# CAN.net
KiCad netlist of a schematic drawn in Altium Designer
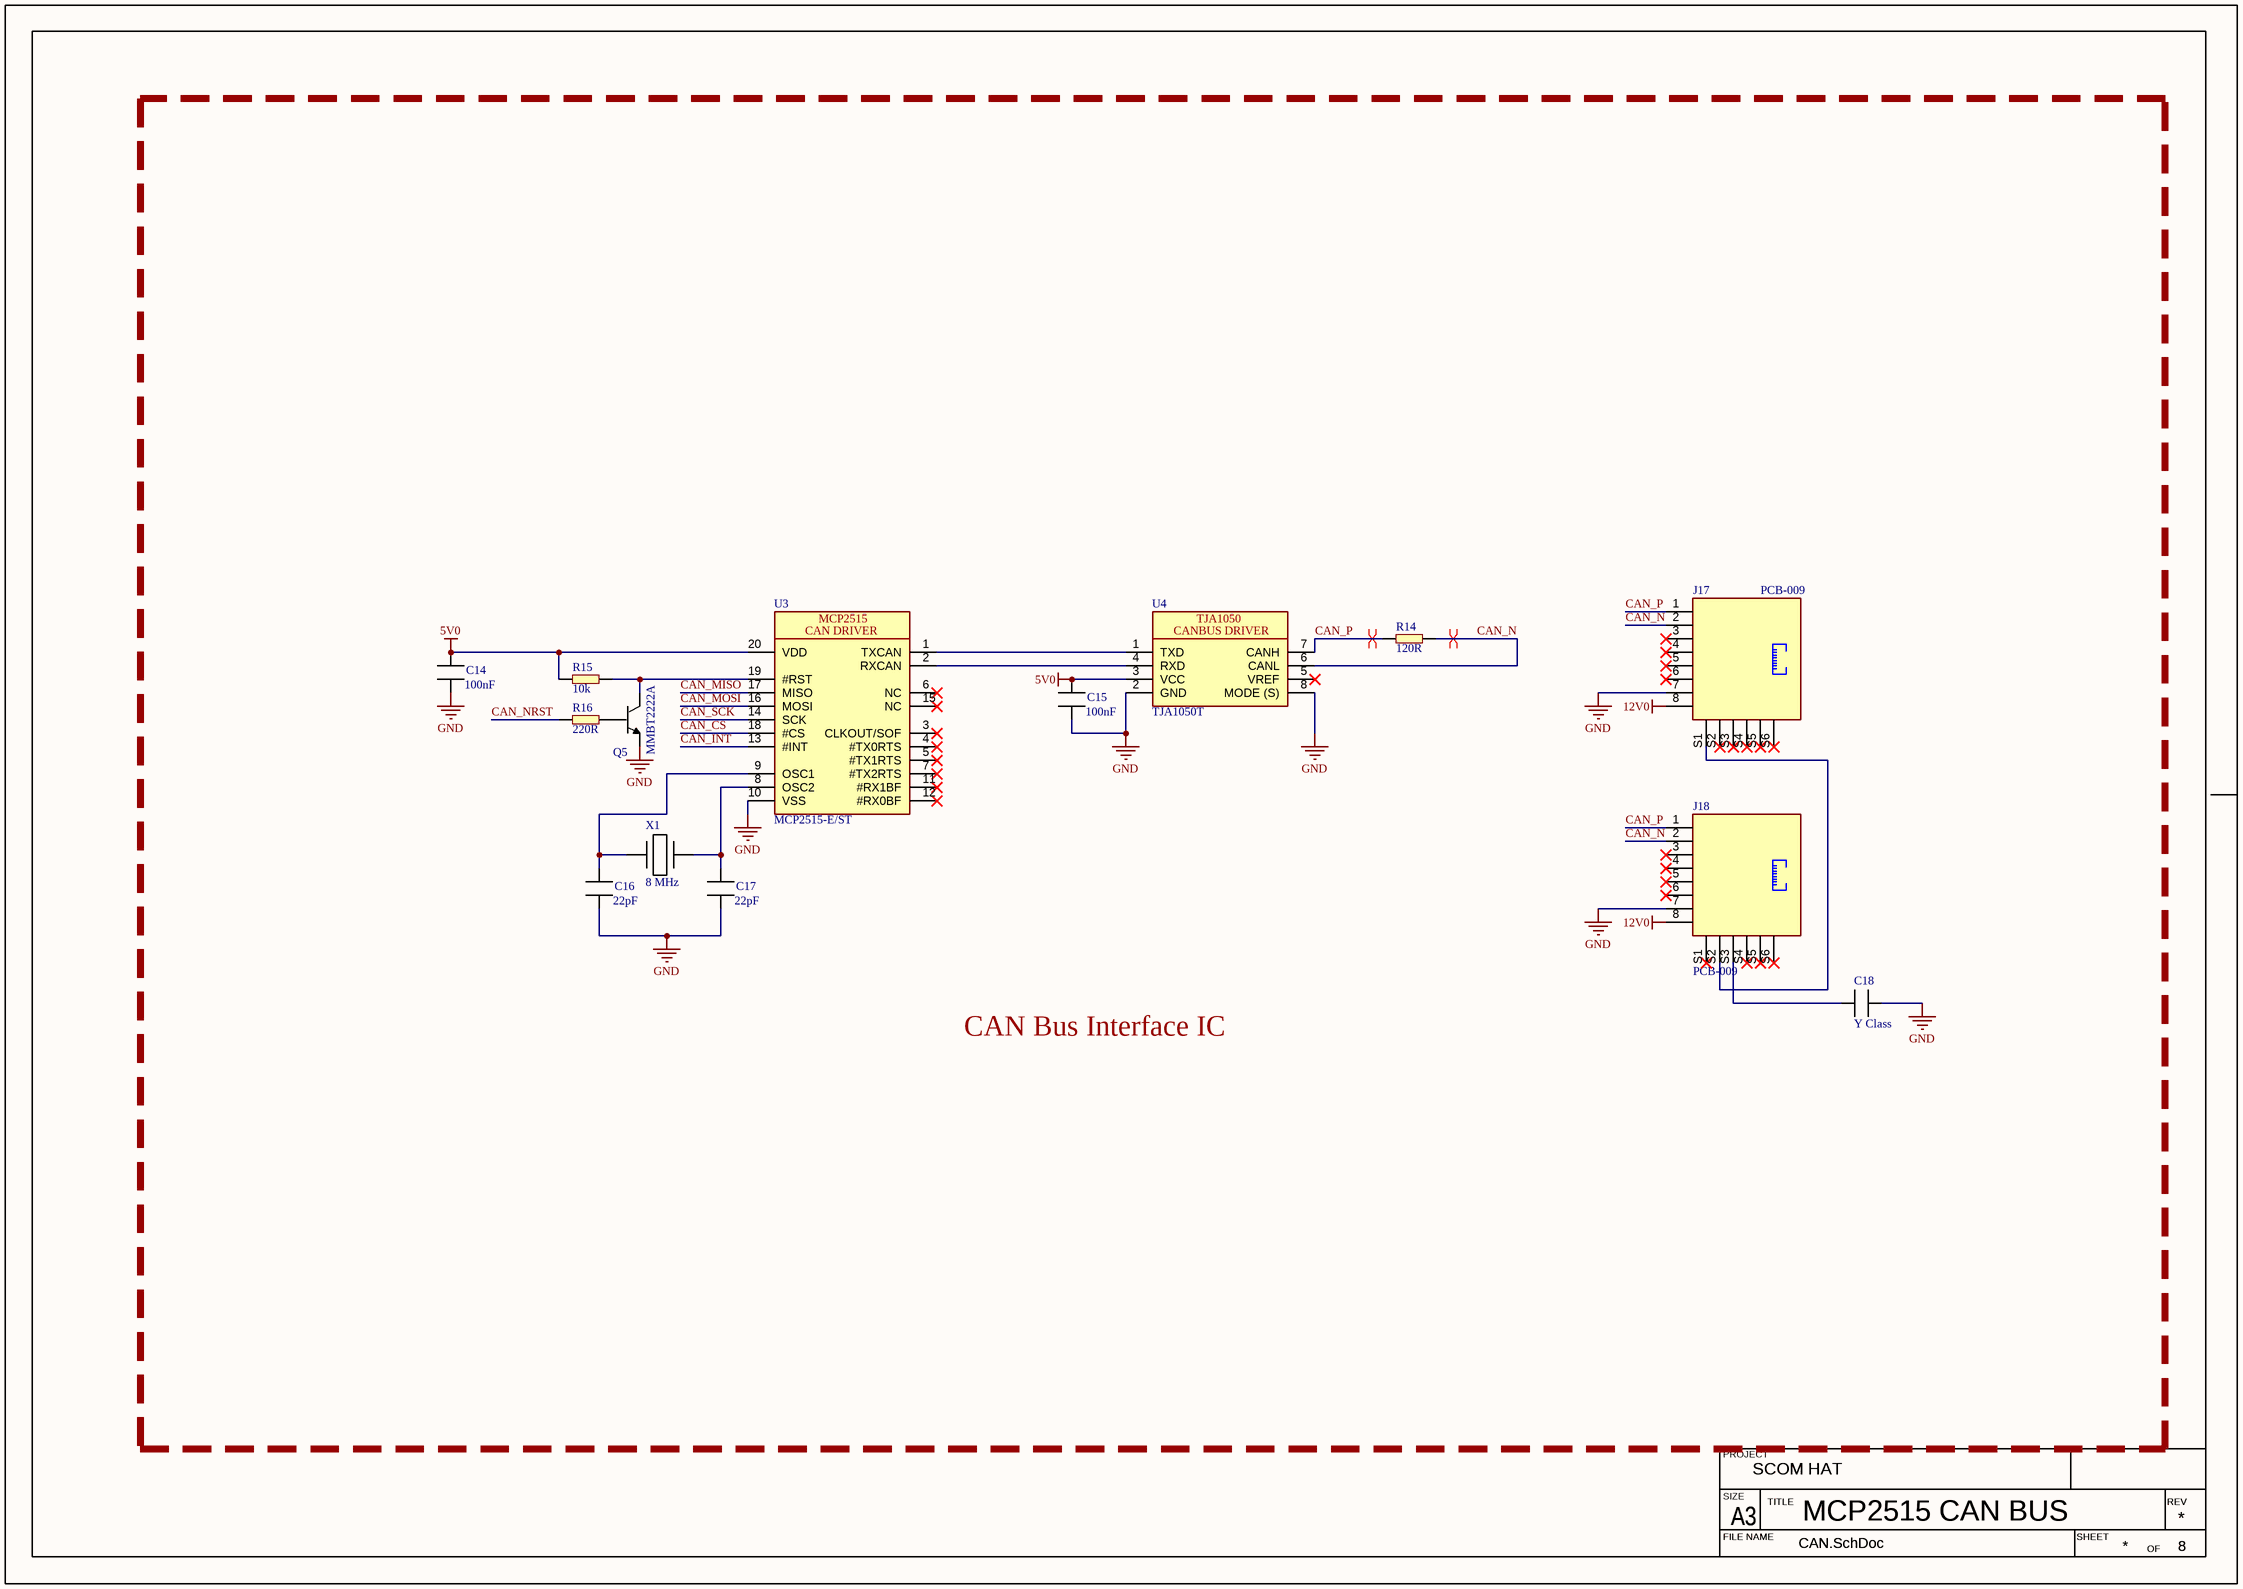
[diagram p0: CAN.SchDoc]

(export (version "E")
  (design (tool "Eeschema 10.0.6"))
  (components
    (comp (ref "C14")
      (value "100nF")
      (footprint "CAPC2012X13L")
      (description "Chip Capacitor, 2-Leads, Body 2.00x1.25mm, IPC High Density")
      (fields (field (name "Comment") "MLCC_0805"))
      (libsource (lib "Capacitor") (part "MLCC_0805"))
    )
    (comp (ref "C15")
      (value "100nF")
      (footprint "CAPC2012X13L")
      (description "Chip Capacitor, 2-Leads, Body 2.00x1.25mm, IPC High Density")
      (fields (field (name "Comment") "MLCC_0805"))
      (libsource (lib "Capacitor") (part "MLCC_0805"))
    )
    (comp (ref "C16")
      (value "22pF")
      (footprint "CAPC2012X13L")
      (description "Chip Capacitor, 2-Leads, Body 2.00x1.25mm, IPC High Density")
      (fields (field (name "Comment") "MLCC_0805"))
      (libsource (lib "Capacitor") (part "MLCC_0805"))
    )
    (comp (ref "C17")
      (value "22pF")
      (footprint "CAPC2012X13L")
      (description "Chip Capacitor, 2-Leads, Body 2.00x1.25mm, IPC High Density")
      (fields (field (name "Comment") "MLCC_0805"))
      (libsource (lib "Capacitor") (part "MLCC_0805"))
    )
    (comp (ref "C18")
      (value "Y Class")
      (footprint "VY1222M43Y5UC63V0")
      (description "Ceramic Capacitor Y5U (E) Radial, Disc")
      (fields (field (name "Comment") "VY1"))
      (libsource (lib "Capacitor") (part "VY1"))
    )
    (comp (ref "J17")
      (value "PCB-009")
      (footprint "PCB-009")
      (description "PCB-009 Robu")
      (fields (field (name "Comment") "ERP_148-3"))
      (libsource (lib "Connectors") (part "RJ45_Top_Entry"))
    )
    (comp (ref "J18")
      (value "PCB-009")
      (footprint "PCB-009")
      (description "PCB-009 Robu")
      (fields (field (name "Comment") "ERP_148-3"))
      (libsource (lib "Connectors") (part "RJ45_Top_Entry"))
    )
    (comp (ref "Q5")
      (value "MMBT2222A")
      (footprint "MMBT2222")
      (fields (field (name "Comment") "ERP_105-1"))
      (libsource (lib "BJT") (part "MMBT2222"))
    )
    (comp (ref "R14")
      (value "120R")
      (footprint "RES_0603")
      (description "RES_0603")
      (fields (field (name "Comment") "ERP_101-1"))
      (libsource (lib "Resistor") (part "RES_0603"))
    )
    (comp (ref "R15")
      (value "10k")
      (footprint "RES_0603")
      (description "RES_0603")
      (fields (field (name "Comment") "ERP_101-1"))
      (libsource (lib "Resistor") (part "RES_0603"))
    )
    (comp (ref "R16")
      (value "220R")
      (footprint "RES_0603")
      (description "RES_0603")
      (fields (field (name "Comment") "ERP_101-1"))
      (libsource (lib "Resistor") (part "RES_0603"))
    )
    (comp (ref "U3")
      (value "MCP2515-E/ST")
      (footprint "MCP2515-ST")
      (description "CAN Interface IC")
      (fields (field (name "Comment") "MCP2515"))
      (libsource (lib "Communication") (part "MCP2515"))
    )
    (comp (ref "U4")
      (value "TJA1050T")
      (footprint "TJA1050T")
      (description "CAN Transceiver IC")
      (fields (field (name "Comment") "TJA1050"))
      (libsource (lib "Communication") (part "TJA1050"))
    )
    (comp (ref "X1")
      (value "8 MHz")
      (footprint "HC-49US")
      (description "CRYSTAL HC-49US 2 Pin")
      (fields (field (name "Comment") "HC-49US"))
      (libsource (lib "Crystal") (part "HC-49US"))
    )
  )
  (nets
    (net (code "1") (name "/CAN_CS") (class "Default")
      (node (ref "U3") (pin "18") (pinfunction "#CS_18") (pintype "passive"))
    )
    (net (code "2") (name "/CAN_INT") (class "Default")
      (node (ref "U3") (pin "13") (pinfunction "#INT_13") (pintype "passive"))
    )
    (net (code "3") (name "/CAN_MISO") (class "Default")
      (node (ref "U3") (pin "17") (pinfunction "MISO_17") (pintype "passive"))
    )
    (net (code "4") (name "/CAN_MOSI") (class "Default")
      (node (ref "U3") (pin "16") (pinfunction "MOSI_16") (pintype "passive"))
    )
    (net (code "5") (name "/CAN_N") (class "Default")
      (node (ref "J17") (pin "2") (pinfunction "2_2") (pintype "passive"))
      (node (ref "J18") (pin "2") (pinfunction "2_2") (pintype "passive"))
      (node (ref "R14") (pin "2") (pinfunction "2_2") (pintype "passive"))
      (node (ref "U4") (pin "6") (pinfunction "CANL_6") (pintype "passive"))
    )
    (net (code "6") (name "/CAN_NRST") (class "Default")
      (node (ref "R16") (pin "1") (pinfunction "1_1") (pintype "passive"))
    )
    (net (code "7") (name "/CAN_P") (class "Default")
      (node (ref "J17") (pin "1") (pinfunction "1_1") (pintype "passive"))
      (node (ref "J18") (pin "1") (pinfunction "1_1") (pintype "passive"))
      (node (ref "R14") (pin "1") (pinfunction "1_1") (pintype "passive"))
      (node (ref "U4") (pin "7") (pinfunction "CANH_7") (pintype "passive"))
    )
    (net (code "8") (name "/CAN_SCK") (class "Default")
      (node (ref "U3") (pin "14") (pinfunction "SCK_14") (pintype "passive"))
    )
    (net (code "9") (name "5V0") (class "Default")
      (node (ref "C14") (pin "1") (pinfunction "1_1") (pintype "passive"))
      (node (ref "C15") (pin "1") (pinfunction "1_1") (pintype "passive"))
      (node (ref "R15") (pin "1") (pinfunction "1_1") (pintype "passive"))
      (node (ref "U3") (pin "20") (pinfunction "VDD_20") (pintype "passive"))
      (node (ref "U4") (pin "3") (pinfunction "VCC_3") (pintype "passive"))
    )
    (net (code "10") (name "12V0") (class "Default")
      (node (ref "J17") (pin "8") (pinfunction "8_8") (pintype "passive"))
      (node (ref "J18") (pin "8") (pinfunction "8_8") (pintype "passive"))
    )
    (net (code "11") (name "GND") (class "Default")
      (node (ref "C14") (pin "2") (pinfunction "2_2") (pintype "passive"))
      (node (ref "C15") (pin "2") (pinfunction "2_2") (pintype "passive"))
      (node (ref "C16") (pin "2") (pinfunction "2_2") (pintype "passive"))
      (node (ref "C17") (pin "2") (pinfunction "2_2") (pintype "passive"))
      (node (ref "C18") (pin "2") (pinfunction "2_2") (pintype "passive"))
      (node (ref "J17") (pin "7") (pinfunction "7_7") (pintype "passive"))
      (node (ref "J18") (pin "7") (pinfunction "7_7") (pintype "passive"))
      (node (ref "Q5") (pin "2") (pinfunction "2_2") (pintype "passive"))
      (node (ref "U3") (pin "10") (pinfunction "VSS_10") (pintype "passive"))
      (node (ref "U4") (pin "2") (pinfunction "GND_2") (pintype "passive"))
      (node (ref "U4") (pin "8") (pinfunction "MODE_(S)_8") (pintype "passive"))
    )
    (net (code "12") (name "Net-(C18-Pad1)") (class "Default")
      (node (ref "C18") (pin "1") (pinfunction "1_1") (pintype "passive"))
      (node (ref "J18") (pin "S3") (pinfunction "S3_S3") (pintype "passive"))
    )
    (net (code "13") (name "Net-(J17-PadS1)") (class "Default")
      (node (ref "J17") (pin "S1") (pinfunction "S1_S1") (pintype "passive"))
      (node (ref "J18") (pin "S2") (pinfunction "S2_S2") (pintype "passive"))
    )
    (net (code "14") (name "Net-(Q5-Pad1)") (class "Default")
      (node (ref "Q5") (pin "1") (pinfunction "1_1") (pintype "passive"))
      (node (ref "R16") (pin "2") (pinfunction "2_2") (pintype "passive"))
    )
    (net (code "15") (name "Net-(U3-#RST)") (class "Default")
      (node (ref "Q5") (pin "3") (pinfunction "3_3") (pintype "passive"))
      (node (ref "R15") (pin "2") (pinfunction "2_2") (pintype "passive"))
      (node (ref "U3") (pin "19") (pinfunction "#RST_19") (pintype "passive"))
    )
    (net (code "16") (name "Net-(U3-OSC1)") (class "Default")
      (node (ref "C16") (pin "1") (pinfunction "1_1") (pintype "passive"))
      (node (ref "U3") (pin "9") (pinfunction "OSC1_9") (pintype "passive"))
      (node (ref "X1") (pin "1") (pinfunction "1_1") (pintype "passive"))
    )
    (net (code "17") (name "Net-(U3-OSC2)") (class "Default")
      (node (ref "C17") (pin "1") (pinfunction "1_1") (pintype "passive"))
      (node (ref "U3") (pin "8") (pinfunction "OSC2_8") (pintype "passive"))
      (node (ref "X1") (pin "2") (pinfunction "2_2") (pintype "passive"))
    )
    (net (code "18") (name "Net-(U3-RXCAN)") (class "Default")
      (node (ref "U3") (pin "2") (pinfunction "RXCAN_2") (pintype "passive"))
      (node (ref "U4") (pin "4") (pinfunction "RXD_4") (pintype "passive"))
    )
    (net (code "19") (name "Net-(U3-TXCAN)") (class "Default")
      (node (ref "U3") (pin "1") (pinfunction "TXCAN_1") (pintype "passive"))
      (node (ref "U4") (pin "1") (pinfunction "TXD_1") (pintype "passive"))
    )
    (net (code "20") (name "unconnected-(J17-Pad3)") (class "Default")
      (node (ref "J17") (pin "3") (pinfunction "3_3") (pintype "passive+no_connect"))
    )
    (net (code "21") (name "unconnected-(J17-Pad4)") (class "Default")
      (node (ref "J17") (pin "4") (pinfunction "4_4") (pintype "passive+no_connect"))
    )
    (net (code "22") (name "unconnected-(J17-Pad5)") (class "Default")
      (node (ref "J17") (pin "5") (pinfunction "5_5") (pintype "passive+no_connect"))
    )
    (net (code "23") (name "unconnected-(J17-Pad6)") (class "Default")
      (node (ref "J17") (pin "6") (pinfunction "6_6") (pintype "passive+no_connect"))
    )
    (net (code "24") (name "unconnected-(J17-PadS2)") (class "Default")
      (node (ref "J17") (pin "S2") (pinfunction "S2_S2") (pintype "passive+no_connect"))
    )
    (net (code "25") (name "unconnected-(J17-PadS3)") (class "Default")
      (node (ref "J17") (pin "S3") (pinfunction "S3_S3") (pintype "passive+no_connect"))
    )
    (net (code "26") (name "unconnected-(J17-PadS4)") (class "Default")
      (node (ref "J17") (pin "S4") (pinfunction "S4_S4") (pintype "passive+no_connect"))
    )
    (net (code "27") (name "unconnected-(J17-PadS5)") (class "Default")
      (node (ref "J17") (pin "S5") (pinfunction "S5_S5") (pintype "passive+no_connect"))
    )
    (net (code "28") (name "unconnected-(J17-PadS6)") (class "Default")
      (node (ref "J17") (pin "S6") (pinfunction "S6_S6") (pintype "passive+no_connect"))
    )
    (net (code "29") (name "unconnected-(J18-Pad3)") (class "Default")
      (node (ref "J18") (pin "3") (pinfunction "3_3") (pintype "passive+no_connect"))
    )
    (net (code "30") (name "unconnected-(J18-Pad4)") (class "Default")
      (node (ref "J18") (pin "4") (pinfunction "4_4") (pintype "passive+no_connect"))
    )
    (net (code "31") (name "unconnected-(J18-Pad5)") (class "Default")
      (node (ref "J18") (pin "5") (pinfunction "5_5") (pintype "passive+no_connect"))
    )
    (net (code "32") (name "unconnected-(J18-Pad6)") (class "Default")
      (node (ref "J18") (pin "6") (pinfunction "6_6") (pintype "passive+no_connect"))
    )
    (net (code "33") (name "unconnected-(J18-PadS1)") (class "Default")
      (node (ref "J18") (pin "S1") (pinfunction "S1_S1") (pintype "passive+no_connect"))
    )
    (net (code "34") (name "unconnected-(J18-PadS4)") (class "Default")
      (node (ref "J18") (pin "S4") (pinfunction "S4_S4") (pintype "passive+no_connect"))
    )
    (net (code "35") (name "unconnected-(J18-PadS5)") (class "Default")
      (node (ref "J18") (pin "S5") (pinfunction "S5_S5") (pintype "passive+no_connect"))
    )
    (net (code "36") (name "unconnected-(J18-PadS6)") (class "Default")
      (node (ref "J18") (pin "S6") (pinfunction "S6_S6") (pintype "passive+no_connect"))
    )
    (net (code "37") (name "unconnected-(U3-#RX0BF-Pad12)") (class "Default")
      (node (ref "U3") (pin "12") (pinfunction "#RX0BF_12") (pintype "passive+no_connect"))
    )
    (net (code "38") (name "unconnected-(U3-#RX1BF-Pad11)") (class "Default")
      (node (ref "U3") (pin "11") (pinfunction "#RX1BF_11") (pintype "passive+no_connect"))
    )
    (net (code "39") (name "unconnected-(U3-#TX0RTS-Pad4)") (class "Default")
      (node (ref "U3") (pin "4") (pinfunction "#TX0RTS_4") (pintype "passive+no_connect"))
    )
    (net (code "40") (name "unconnected-(U3-#TX1RTS-Pad5)") (class "Default")
      (node (ref "U3") (pin "5") (pinfunction "#TX1RTS_5") (pintype "passive+no_connect"))
    )
    (net (code "41") (name "unconnected-(U3-#TX2RTS-Pad7)") (class "Default")
      (node (ref "U3") (pin "7") (pinfunction "#TX2RTS_7") (pintype "passive+no_connect"))
    )
    (net (code "42") (name "unconnected-(U3-CLKOUT{slash}SOF-Pad3)") (class "Default")
      (node (ref "U3") (pin "3") (pinfunction "CLKOUT/SOF_3") (pintype "passive+no_connect"))
    )
    (net (code "43") (name "unconnected-(U3-NC-Pad6)") (class "Default")
      (node (ref "U3") (pin "6") (pinfunction "NC_6") (pintype "passive+no_connect"))
    )
    (net (code "44") (name "unconnected-(U3-NC-Pad15)") (class "Default")
      (node (ref "U3") (pin "15") (pinfunction "NC_15") (pintype "passive+no_connect"))
    )
    (net (code "45") (name "unconnected-(U4-VREF-Pad5)") (class "Default")
      (node (ref "U4") (pin "5") (pinfunction "VREF_5") (pintype "passive+no_connect"))
    )
  )
)
